# TopLevel.net
KiCad netlist of a schematic drawn in Altium Designer
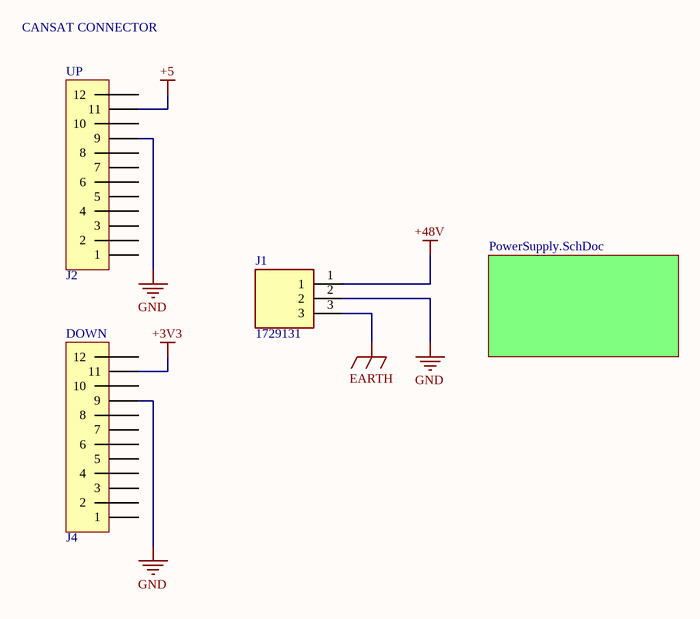
[diagram p0: TopLevel.SchDoc]

(export (version "E")
  (design (tool "Eeschema 10.0.6"))
  (components
    (comp (ref "J1")
      (value "1729131")
      (footprint "SamacSys:1729131")
      (description "Connector")
      (fields (field (name "MOUSER PART NUMBER") "651-1729131"))
      (libsource (lib "*") (part "1729131"))
    )
    (comp (ref "J2")
      (value "*")
      (footprint "PINHEADER2X6 P2.54 SIDE MOUNT")
      (description "Plug connector")
      (libsource (lib "PinHeader") (part "PinHeader2x6"))
    )
    (comp (ref "J4")
      (value "*")
      (footprint "PINHEADER2X6 P2.54 SIDE MOUNT")
      (description "Plug connector")
      (libsource (lib "PinHeader") (part "PinHeader2x6"))
    )
  )
  (nets
    (net (code "1") (name "+3V3") (class "Default")
      (node (ref "J4") (pin "11") (pinfunction "11_11") (pintype "passive"))
    )
    (net (code "2") (name "+5") (class "Default")
      (node (ref "J2") (pin "11") (pinfunction "11_11") (pintype "passive"))
    )
    (net (code "3") (name "+48V") (class "Default")
      (node (ref "J1") (pin "1") (pinfunction "1_1") (pintype "passive"))
    )
    (net (code "4") (name "EARTH") (class "Default")
      (node (ref "J1") (pin "3") (pinfunction "3_3") (pintype "passive"))
    )
    (net (code "5") (name "GND") (class "Default")
      (node (ref "J1") (pin "2") (pinfunction "2_2") (pintype "passive"))
      (node (ref "J2") (pin "9") (pinfunction "9_9") (pintype "passive"))
      (node (ref "J4") (pin "9") (pinfunction "9_9") (pintype "passive"))
    )
    (net (code "6") (name "unconnected-(J2-Pad1)") (class "Default")
      (node (ref "J2") (pin "1") (pinfunction "1_1") (pintype "passive"))
    )
    (net (code "7") (name "unconnected-(J2-Pad2)") (class "Default")
      (node (ref "J2") (pin "2") (pinfunction "2_2") (pintype "passive"))
    )
    (net (code "8") (name "unconnected-(J2-Pad3)") (class "Default")
      (node (ref "J2") (pin "3") (pinfunction "3_3") (pintype "passive"))
    )
    (net (code "9") (name "unconnected-(J2-Pad4)") (class "Default")
      (node (ref "J2") (pin "4") (pinfunction "4_4") (pintype "passive"))
    )
    (net (code "10") (name "unconnected-(J2-Pad5)") (class "Default")
      (node (ref "J2") (pin "5") (pinfunction "5_5") (pintype "passive"))
    )
    (net (code "11") (name "unconnected-(J2-Pad6)") (class "Default")
      (node (ref "J2") (pin "6") (pinfunction "6_6") (pintype "passive"))
    )
    (net (code "12") (name "unconnected-(J2-Pad7)") (class "Default")
      (node (ref "J2") (pin "7") (pinfunction "7_7") (pintype "passive"))
    )
    (net (code "13") (name "unconnected-(J2-Pad8)") (class "Default")
      (node (ref "J2") (pin "8") (pinfunction "8_8") (pintype "passive"))
    )
    (net (code "14") (name "unconnected-(J2-Pad10)") (class "Default")
      (node (ref "J2") (pin "10") (pinfunction "10_10") (pintype "passive"))
    )
    (net (code "15") (name "unconnected-(J2-Pad12)") (class "Default")
      (node (ref "J2") (pin "12") (pinfunction "12_12") (pintype "passive"))
    )
    (net (code "16") (name "unconnected-(J4-Pad1)") (class "Default")
      (node (ref "J4") (pin "1") (pinfunction "1_1") (pintype "passive"))
    )
    (net (code "17") (name "unconnected-(J4-Pad2)") (class "Default")
      (node (ref "J4") (pin "2") (pinfunction "2_2") (pintype "passive"))
    )
    (net (code "18") (name "unconnected-(J4-Pad3)") (class "Default")
      (node (ref "J4") (pin "3") (pinfunction "3_3") (pintype "passive"))
    )
    (net (code "19") (name "unconnected-(J4-Pad4)") (class "Default")
      (node (ref "J4") (pin "4") (pinfunction "4_4") (pintype "passive"))
    )
    (net (code "20") (name "unconnected-(J4-Pad5)") (class "Default")
      (node (ref "J4") (pin "5") (pinfunction "5_5") (pintype "passive"))
    )
    (net (code "21") (name "unconnected-(J4-Pad6)") (class "Default")
      (node (ref "J4") (pin "6") (pinfunction "6_6") (pintype "passive"))
    )
    (net (code "22") (name "unconnected-(J4-Pad7)") (class "Default")
      (node (ref "J4") (pin "7") (pinfunction "7_7") (pintype "passive"))
    )
    (net (code "23") (name "unconnected-(J4-Pad8)") (class "Default")
      (node (ref "J4") (pin "8") (pinfunction "8_8") (pintype "passive"))
    )
    (net (code "24") (name "unconnected-(J4-Pad10)") (class "Default")
      (node (ref "J4") (pin "10") (pinfunction "10_10") (pintype "passive"))
    )
    (net (code "25") (name "unconnected-(J4-Pad12)") (class "Default")
      (node (ref "J4") (pin "12") (pinfunction "12_12") (pintype "passive"))
    )
  )
)
